# Sensor_Board_Required.net
KiCad netlist of a schematic drawn in EAGLE
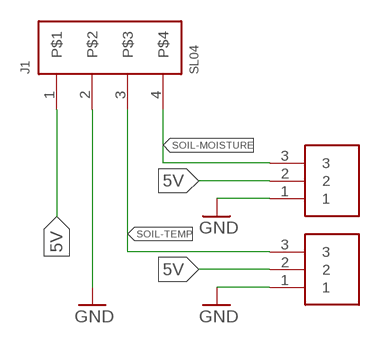
[diagram p0: schematic, sheet 1]

(export (version "E")
  (design (tool "Eeschema 10.0.6"))
  (components
    (comp (ref "J1")
      (value "SL04")
      (footprint "eagle-import:MOLEX_SL_04_TH")
      (libsource (lib "eagle-import") (part "SL04"))
    )
    (comp (ref "J2")
      (value "SL03THROUGH_HOLE")
      (footprint "eagle-import:MOLEX_SL_03_TH")
      (fields (field (name "PARTNO") "0705550002"))
      (libsource (lib "eagle-import") (part "SL03THROUGH_HOLE"))
    )
    (comp (ref "J3")
      (value "SL03THROUGH_HOLE")
      (footprint "eagle-import:MOLEX_SL_03_TH")
      (fields (field (name "PARTNO") "0705550002"))
      (libsource (lib "eagle-import") (part "SL03THROUGH_HOLE"))
    )
  )
  (nets
    (net (code "1") (name "5V") (class "Default")
      (node (ref "J1") (pin "1") (pinfunction "P$1_1") (pintype "bidirectional"))
      (node (ref "J2") (pin "2") (pinfunction "2_2") (pintype "bidirectional"))
      (node (ref "J3") (pin "2") (pinfunction "2_2") (pintype "bidirectional"))
    )
    (net (code "2") (name "GND") (class "Default")
      (node (ref "J1") (pin "2") (pinfunction "P$2_2") (pintype "bidirectional"))
      (node (ref "J2") (pin "1") (pinfunction "1_1") (pintype "bidirectional"))
      (node (ref "J3") (pin "1") (pinfunction "1_1") (pintype "bidirectional"))
    )
    (net (code "3") (name "SOIL-MOISTURE") (class "Default")
      (node (ref "J1") (pin "4") (pinfunction "P$4_4") (pintype "bidirectional"))
      (node (ref "J2") (pin "3") (pinfunction "3_3") (pintype "bidirectional"))
    )
    (net (code "4") (name "SOIL-TEMP") (class "Default")
      (node (ref "J1") (pin "3") (pinfunction "P$3_3") (pintype "bidirectional"))
      (node (ref "J3") (pin "3") (pinfunction "3_3") (pintype "bidirectional"))
    )
  )
)
